# PumpMinder_v2_1.net
KiCad netlist of a schematic drawn in Altium Designer
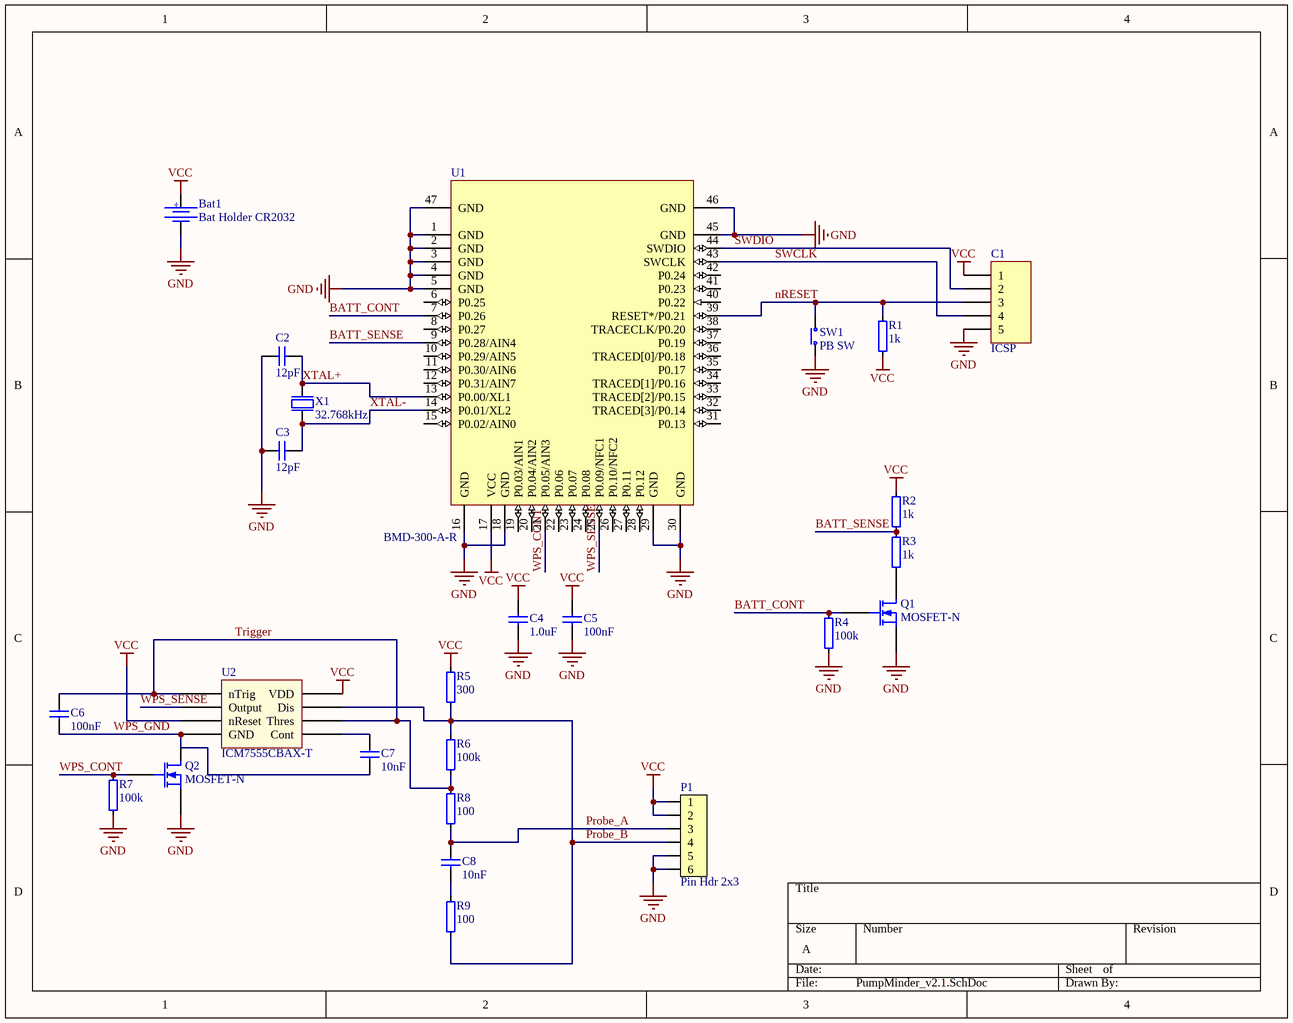
[diagram p0: PumpMinder_v2.1.SchDoc]

(export (version "E")
  (design (tool "Eeschema 10.0.6"))
  (components
    (comp (ref "Bat1")
      (value "Bat Holder CR2032")
      (footprint "CR2032_HOLDER_SMD")
      (description "Bat Holder CR2032 SMD")
      (fields
        (field (name "MANUFACTURER") "Keystone")
        (field (name "MANUFACTURER PART NUMBER") "3002")
        (field (name "PUBLISHER") "Nordic Semiconductor")
      )
      (libsource (lib "pca10040") (part "Battery"))
    )
    (comp (ref "C1") (value "ICSP") (footprint "TC2030-MCP") (libsource (lib "TC2030") (part "ICSP")))
    (comp (ref "C2")
      (value "12pF")
      (footprint "CAPC1005X04L")
      (description "Capacitor, NP0, ±0.1pF")
      (fields (field (name "PART NUMBER") "C0402-1.2p") (field (name "PUBLISHER") "Nordic Semiconductor"))
      (libsource (lib "pca10040") (part "CAP_0402"))
    )
    (comp (ref "C3")
      (value "12pF")
      (footprint "CAPC1005X04L")
      (description "Capacitor, NP0, ±0.1pF")
      (fields (field (name "PART NUMBER") "C0402-1.2p") (field (name "PUBLISHER") "Nordic Semiconductor"))
      (libsource (lib "pca10040") (part "CAP_0402"))
    )
    (comp (ref "C4")
      (value "1.0uF")
      (footprint "CAPC1608X06L")
      (description "Capacitor, X5R, ±10%")
      (fields (field (name "PART NUMBER") "C0603-4µ7") (field (name "PUBLISHER") "Nordic Semiconductor"))
      (libsource (lib "pca10040") (part "CAP_0603"))
    )
    (comp (ref "C5")
      (value "100nF")
      (footprint "CAPC1005X04L")
      (description "Capacitor, NP0, ±0.1pF")
      (fields (field (name "PART NUMBER") "C0402-1.2p") (field (name "PUBLISHER") "Nordic Semiconductor"))
      (libsource (lib "pca10040") (part "CAP_0402"))
    )
    (comp (ref "C6")
      (value "100nF")
      (footprint "CAPC1005X04L")
      (description "Capacitor, NP0, ±0.1pF")
      (fields (field (name "PART NUMBER") "C0402-1.2p") (field (name "PUBLISHER") "Nordic Semiconductor"))
      (libsource (lib "pca10040") (part "CAP_0402"))
    )
    (comp (ref "C7")
      (value "10nF")
      (footprint "CAPC1005X04L")
      (description "Capacitor, NP0, ±0.1pF")
      (fields (field (name "PART NUMBER") "C0402-1.2p") (field (name "PUBLISHER") "Nordic Semiconductor"))
      (libsource (lib "pca10040") (part "CAP_0402"))
    )
    (comp (ref "C8")
      (value "10nF")
      (footprint "CAPC1005X04L")
      (description "Capacitor, NP0, ±0.1pF")
      (fields (field (name "PART NUMBER") "C0402-1.2p") (field (name "PUBLISHER") "Nordic Semiconductor"))
      (libsource (lib "pca10040") (part "CAP_0402"))
    )
    (comp (ref "P1")
      (value "Pin Hdr 2x3")
      (footprint "Molex 15-91-2060")
      (description "Pin Header 2x3, 2.54mm (100mil) SMD")
      (fields
        (field (name "PART NUMBER") "Pin Header 2x3 SMD")
        (field (name "MANUFACTURER") "Molex")
        (field (name "PUBLISHER") "Nordic Semiconductor")
      )
      (libsource (lib "pca10040") (part "Pin Header 2x3 SMD"))
    )
    (comp (ref "Q1")
      (value "MOSFET-N")
      (footprint "SOT-23_L")
      (description "N-Channel MOSFET")
      (fields (field (name "PUBLISHER") "Altium Limited"))
      (libsource (lib "Custom_Library") (part "MOSFET-N"))
    )
    (comp (ref "Q2")
      (value "MOSFET-N")
      (footprint "SOT-23_L")
      (description "N-Channel MOSFET")
      (fields (field (name "PUBLISHER") "Altium Limited"))
      (libsource (lib "Custom_Library") (part "MOSFET-N"))
    )
    (comp (ref "R1")
      (value "1k")
      (footprint "RESC1005X04L")
      (description "Not mounted")
      (fields (field (name "PART NUMBER") "R0402-N.C.") (field (name "PUBLISHER") "Nordic Semiconductor"))
      (libsource (lib "pca10040") (part "RES_0402"))
    )
    (comp (ref "R2")
      (value "1k")
      (footprint "RESC1005X04L")
      (description "Not mounted")
      (fields (field (name "PART NUMBER") "R0402-N.C.") (field (name "PUBLISHER") "Nordic Semiconductor"))
      (libsource (lib "pca10040") (part "RES_0402"))
    )
    (comp (ref "R3")
      (value "1k")
      (footprint "RESC1005X04L")
      (description "Not mounted")
      (fields (field (name "PART NUMBER") "R0402-N.C.") (field (name "PUBLISHER") "Nordic Semiconductor"))
      (libsource (lib "pca10040") (part "RES_0402"))
    )
    (comp (ref "R4")
      (value "100k")
      (footprint "RESC1005X04L")
      (description "Not mounted")
      (fields (field (name "PART NUMBER") "R0402-N.C.") (field (name "PUBLISHER") "Nordic Semiconductor"))
      (libsource (lib "pca10040") (part "RES_0402"))
    )
    (comp (ref "R5")
      (value "300")
      (footprint "RESC1005X04L")
      (description "Not mounted")
      (fields (field (name "PART NUMBER") "R0402-N.C.") (field (name "PUBLISHER") "Nordic Semiconductor"))
      (libsource (lib "pca10040") (part "RES_0402"))
    )
    (comp (ref "R6")
      (value "100k")
      (footprint "RESC1005X04L")
      (description "Not mounted")
      (fields (field (name "PART NUMBER") "R0402-N.C.") (field (name "PUBLISHER") "Nordic Semiconductor"))
      (libsource (lib "pca10040") (part "RES_0402"))
    )
    (comp (ref "R7")
      (value "100k")
      (footprint "RESC1005X04L")
      (description "Not mounted")
      (fields (field (name "PART NUMBER") "R0402-N.C.") (field (name "PUBLISHER") "Nordic Semiconductor"))
      (libsource (lib "pca10040") (part "RES_0402"))
    )
    (comp (ref "R8")
      (value "100")
      (footprint "RESC1005X04L")
      (description "Not mounted")
      (fields (field (name "PART NUMBER") "R0402-N.C.") (field (name "PUBLISHER") "Nordic Semiconductor"))
      (libsource (lib "pca10040") (part "RES_0402"))
    )
    (comp (ref "R9")
      (value "100")
      (footprint "RESC1005X04L")
      (description "Not mounted")
      (fields (field (name "PART NUMBER") "R0402-N.C.") (field (name "PUBLISHER") "Nordic Semiconductor"))
      (libsource (lib "pca10040") (part "RES_0402"))
    )
    (comp (ref "SW1")
      (value "PB SW")
      (footprint "ALPS_SKHUxxx010_WO_GND")
      (description "ALPS - SKHUALE010 - Tactile Switch, SPNO, SMD, 6.5x6.2x2.5mm")
      (fields
        (field (name "PART NUMBER") "ALPS_SKHUALE010")
        (field (name "MANUFACTURER") "Alps")
        (field (name "PUBLISHER") "Nordic Semiconductor")
      )
      (libsource (lib "pca10040") (part "SW-PB"))
    )
    (comp (ref "U1")
      (value "BMD-300")
      (footprint "BMD-300")
      (description "Bluetooth 4.2 LE Module, nRF52832, 512kB Flash, 64kB RAM")
      (fields
        (field (name "PART NUMBER") "BMD-300-A")
        (field (name "MANUFACTURER") "Rigado")
        (field (name "MANUFACTURER P/N") "BMD-300-A-R")
        (field (name "ADDED BY") "Cam N")
      )
      (libsource (lib "BMD-300") (part "BMD-300-A"))
    )
    (comp (ref "U2")
      (value "ICM7555CBAX-T")
      (footprint "SOIC127P600X175-8N")
      (libsource (lib "Custom_Library") (part "555 Timer"))
    )
    (comp (ref "X1")
      (value "32.768kHz")
      (footprint "XTAL_3215")
      (description "EPSON TOYOCOM - FC-135 32.768KHZ ±20PPM,9.0PF - CRYSTAL, SM, WATCH")
      (fields
        (field (name "PART NUMBER") "XTAL_FC-135 32.768k")
        (field (name "MANUFACTURER") "Epson Toyocom")
        (field (name "PUBLISHER") "Nordic Semiconductor")
      )
      (libsource (lib "pca10040") (part "XTAL_SMD3215"))
    )
  )
  (nets
    (net (code "1") (name "/BATT_CONT") (class "Default")
      (node (ref "Q1") (pin "2") (pinfunction "G_2") (pintype "passive"))
      (node (ref "R4") (pin "1") (pinfunction "1_1") (pintype "passive"))
      (node (ref "U1") (pin "7") (pinfunction "P0.26_7") (pintype "bidirectional"))
    )
    (net (code "2") (name "/BATT_SENSE") (class "Default")
      (node (ref "R2") (pin "2") (pinfunction "2_2") (pintype "passive"))
      (node (ref "R3") (pin "1") (pinfunction "1_1") (pintype "passive"))
      (node (ref "U1") (pin "9") (pinfunction "P0.28/AIN4_9") (pintype "bidirectional"))
    )
    (net (code "3") (name "/Probe_A") (class "Default")
      (node (ref "C8") (pin "1") (pinfunction "1_1") (pintype "passive"))
      (node (ref "P1") (pin "3") (pinfunction "3_3") (pintype "power_in"))
      (node (ref "R8") (pin "1") (pinfunction "1_1") (pintype "passive"))
    )
    (net (code "4") (name "/Probe_B") (class "Default")
      (node (ref "P1") (pin "4") (pinfunction "4_4") (pintype "power_in"))
      (node (ref "R5") (pin "1") (pinfunction "1_1") (pintype "passive"))
      (node (ref "R6") (pin "2") (pinfunction "2_2") (pintype "passive"))
      (node (ref "R9") (pin "1") (pinfunction "1_1") (pintype "passive"))
      (node (ref "U2") (pin "7") (pinfunction "Dis_7") (pintype "passive"))
    )
    (net (code "5") (name "/SWCLK") (class "Default")
      (node (ref "C1") (pin "4") (pinfunction "4_4") (pintype "passive"))
      (node (ref "U1") (pin "43") (pinfunction "SWCLK_43") (pintype "bidirectional"))
    )
    (net (code "6") (name "/SWDIO") (class "Default")
      (node (ref "C1") (pin "2") (pinfunction "2_2") (pintype "passive"))
      (node (ref "U1") (pin "44") (pinfunction "SWDIO_44") (pintype "bidirectional"))
    )
    (net (code "7") (name "/Trigger") (class "Default")
      (node (ref "C6") (pin "1") (pinfunction "1_1") (pintype "passive"))
      (node (ref "R6") (pin "1") (pinfunction "1_1") (pintype "passive"))
      (node (ref "R8") (pin "2") (pinfunction "2_2") (pintype "passive"))
      (node (ref "U2") (pin "2") (pinfunction "nTrig_2") (pintype "passive"))
      (node (ref "U2") (pin "6") (pinfunction "Thres_6") (pintype "passive"))
    )
    (net (code "8") (name "/WPS_CONT") (class "Default")
      (node (ref "Q2") (pin "2") (pinfunction "G_2") (pintype "passive"))
      (node (ref "R7") (pin "1") (pinfunction "1_1") (pintype "passive"))
      (node (ref "U1") (pin "21") (pinfunction "P0.05/AIN3_21") (pintype "bidirectional"))
    )
    (net (code "9") (name "/WPS_GND") (class "Default")
      (node (ref "C6") (pin "2") (pinfunction "2_2") (pintype "passive"))
      (node (ref "C7") (pin "2") (pinfunction "2_2") (pintype "passive"))
      (node (ref "Q2") (pin "1") (pinfunction "D_1") (pintype "passive"))
      (node (ref "U2") (pin "1") (pinfunction "GND_1") (pintype "passive"))
    )
    (net (code "10") (name "/WPS_SENSE") (class "Default")
      (node (ref "U1") (pin "25") (pinfunction "P0.09/NFC1_25") (pintype "bidirectional"))
      (node (ref "U2") (pin "3") (pinfunction "Output_3") (pintype "passive"))
    )
    (net (code "11") (name "/XTAL+") (class "Default")
      (node (ref "C2") (pin "2") (pinfunction "2_2") (pintype "passive"))
      (node (ref "U1") (pin "13") (pinfunction "P0.00/XL1_13") (pintype "bidirectional"))
      (node (ref "X1") (pin "2") (pinfunction "out_2") (pintype "passive"))
    )
    (net (code "12") (name "/XTAL-") (class "Default")
      (node (ref "C3") (pin "2") (pinfunction "2_2") (pintype "passive"))
      (node (ref "U1") (pin "14") (pinfunction "P0.01/XL2_14") (pintype "bidirectional"))
      (node (ref "X1") (pin "1") (pinfunction "inp_1") (pintype "passive"))
    )
    (net (code "13") (name "/nRESET") (class "Default")
      (node (ref "C1") (pin "3") (pinfunction "3_3") (pintype "passive"))
      (node (ref "R1") (pin "1") (pinfunction "1_1") (pintype "passive"))
      (node (ref "SW1") (pin "1") (pinfunction "N.O_1") (pintype "passive"))
      (node (ref "U1") (pin "39") (pinfunction "RESET*/P0.21_39") (pintype "bidirectional"))
    )
    (net (code "14") (name "GND") (class "Default")
      (node (ref "Bat1") (pin "2") (pintype "passive"))
      (node (ref "C1") (pin "5") (pinfunction "5_5") (pintype "passive"))
      (node (ref "C2") (pin "1") (pinfunction "1_1") (pintype "passive"))
      (node (ref "C3") (pin "1") (pinfunction "1_1") (pintype "passive"))
      (node (ref "C4") (pin "1") (pinfunction "1_1") (pintype "passive"))
      (node (ref "C5") (pin "1") (pinfunction "1_1") (pintype "passive"))
      (node (ref "P1") (pin "5") (pinfunction "5_5") (pintype "power_in"))
      (node (ref "P1") (pin "6") (pinfunction "6_6") (pintype "power_in"))
      (node (ref "Q1") (pin "3") (pinfunction "S_3") (pintype "passive"))
      (node (ref "Q2") (pin "3") (pinfunction "S_3") (pintype "passive"))
      (node (ref "R4") (pin "2") (pinfunction "2_2") (pintype "passive"))
      (node (ref "R7") (pin "2") (pinfunction "2_2") (pintype "passive"))
      (node (ref "SW1") (pin "2") (pinfunction "COM_2") (pintype "passive"))
      (node (ref "U1") (pin "1") (pinfunction "GND_1") (pintype "power_in"))
      (node (ref "U1") (pin "16") (pinfunction "GND_16") (pintype "power_in"))
      (node (ref "U1") (pin "18") (pinfunction "GND_18") (pintype "power_in"))
      (node (ref "U1") (pin "2") (pinfunction "GND_2") (pintype "power_in"))
      (node (ref "U1") (pin "29") (pinfunction "GND_29") (pintype "power_in"))
      (node (ref "U1") (pin "3") (pinfunction "GND_3") (pintype "power_in"))
      (node (ref "U1") (pin "30") (pinfunction "GND_30") (pintype "power_in"))
      (node (ref "U1") (pin "4") (pinfunction "GND_4") (pintype "power_in"))
      (node (ref "U1") (pin "45") (pinfunction "GND_45") (pintype "power_in"))
      (node (ref "U1") (pin "46") (pinfunction "GND_46") (pintype "power_in"))
      (node (ref "U1") (pin "47") (pinfunction "GND_47") (pintype "power_in"))
      (node (ref "U1") (pin "5") (pinfunction "GND_5") (pintype "power_in"))
    )
    (net (code "15") (name "Net-(C8-Pad2)") (class "Default")
      (node (ref "C8") (pin "2") (pinfunction "2_2") (pintype "passive"))
      (node (ref "R9") (pin "2") (pinfunction "2_2") (pintype "passive"))
    )
    (net (code "16") (name "Net-(Q1-D)") (class "Default")
      (node (ref "Q1") (pin "1") (pinfunction "D_1") (pintype "passive"))
      (node (ref "R3") (pin "2") (pinfunction "2_2") (pintype "passive"))
    )
    (net (code "17") (name "Net-(U2-Cont)") (class "Default")
      (node (ref "C7") (pin "1") (pinfunction "1_1") (pintype "passive"))
      (node (ref "U2") (pin "5") (pinfunction "Cont_5") (pintype "passive"))
    )
    (net (code "18") (name "VCC") (class "Default")
      (node (ref "Bat1") (pin "1") (pintype "passive"))
      (node (ref "C1") (pin "1") (pinfunction "1_1") (pintype "passive"))
      (node (ref "C4") (pin "2") (pinfunction "2_2") (pintype "passive"))
      (node (ref "C5") (pin "2") (pinfunction "2_2") (pintype "passive"))
      (node (ref "P1") (pin "1") (pinfunction "1_1") (pintype "passive"))
      (node (ref "P1") (pin "2") (pinfunction "2_2") (pintype "passive"))
      (node (ref "R1") (pin "2") (pinfunction "2_2") (pintype "passive"))
      (node (ref "R2") (pin "1") (pinfunction "1_1") (pintype "passive"))
      (node (ref "R5") (pin "2") (pinfunction "2_2") (pintype "passive"))
      (node (ref "U1") (pin "17") (pinfunction "VCC_17") (pintype "power_in"))
      (node (ref "U2") (pin "4") (pinfunction "nReset_4") (pintype "passive"))
      (node (ref "U2") (pin "8") (pinfunction "VDD_8") (pintype "passive"))
    )
    (net (code "19") (name "unconnected-(U1-P0.02{slash}AIN0-Pad15)") (class "Default")
      (node (ref "U1") (pin "15") (pinfunction "P0.02/AIN0_15") (pintype "bidirectional"))
    )
    (net (code "20") (name "unconnected-(U1-P0.03{slash}AIN1-Pad19)") (class "Default")
      (node (ref "U1") (pin "19") (pinfunction "P0.03/AIN1_19") (pintype "bidirectional"))
    )
    (net (code "21") (name "unconnected-(U1-P0.04{slash}AIN2-Pad20)") (class "Default")
      (node (ref "U1") (pin "20") (pinfunction "P0.04/AIN2_20") (pintype "bidirectional"))
    )
    (net (code "22") (name "unconnected-(U1-P0.06-Pad22)") (class "Default")
      (node (ref "U1") (pin "22") (pinfunction "P0.06_22") (pintype "bidirectional"))
    )
    (net (code "23") (name "unconnected-(U1-P0.07-Pad23)") (class "Default")
      (node (ref "U1") (pin "23") (pinfunction "P0.07_23") (pintype "bidirectional"))
    )
    (net (code "24") (name "unconnected-(U1-P0.08-Pad24)") (class "Default")
      (node (ref "U1") (pin "24") (pinfunction "P0.08_24") (pintype "bidirectional"))
    )
    (net (code "25") (name "unconnected-(U1-P0.10{slash}NFC2-Pad26)") (class "Default")
      (node (ref "U1") (pin "26") (pinfunction "P0.10/NFC2_26") (pintype "bidirectional"))
    )
    (net (code "26") (name "unconnected-(U1-P0.11-Pad27)") (class "Default")
      (node (ref "U1") (pin "27") (pinfunction "P0.11_27") (pintype "bidirectional"))
    )
    (net (code "27") (name "unconnected-(U1-P0.12-Pad28)") (class "Default")
      (node (ref "U1") (pin "28") (pinfunction "P0.12_28") (pintype "bidirectional"))
    )
    (net (code "28") (name "unconnected-(U1-P0.13-Pad31)") (class "Default")
      (node (ref "U1") (pin "31") (pinfunction "P0.13_31") (pintype "bidirectional"))
    )
    (net (code "29") (name "unconnected-(U1-P0.17-Pad35)") (class "Default")
      (node (ref "U1") (pin "35") (pinfunction "P0.17_35") (pintype "bidirectional"))
    )
    (net (code "30") (name "unconnected-(U1-P0.19-Pad37)") (class "Default")
      (node (ref "U1") (pin "37") (pinfunction "P0.19_37") (pintype "bidirectional"))
    )
    (net (code "31") (name "unconnected-(U1-P0.22-Pad40)") (class "Default")
      (node (ref "U1") (pin "40") (pinfunction "P0.22_40") (pintype "input"))
    )
    (net (code "32") (name "unconnected-(U1-P0.23-Pad41)") (class "Default")
      (node (ref "U1") (pin "41") (pinfunction "P0.23_41") (pintype "bidirectional"))
    )
    (net (code "33") (name "unconnected-(U1-P0.24-Pad42)") (class "Default")
      (node (ref "U1") (pin "42") (pinfunction "P0.24_42") (pintype "bidirectional"))
    )
    (net (code "34") (name "unconnected-(U1-P0.25-Pad6)") (class "Default")
      (node (ref "U1") (pin "6") (pinfunction "P0.25_6") (pintype "bidirectional"))
    )
    (net (code "35") (name "unconnected-(U1-P0.27-Pad8)") (class "Default")
      (node (ref "U1") (pin "8") (pinfunction "P0.27_8") (pintype "bidirectional"))
    )
    (net (code "36") (name "unconnected-(U1-P0.29{slash}AIN5-Pad10)") (class "Default")
      (node (ref "U1") (pin "10") (pinfunction "P0.29/AIN5_10") (pintype "bidirectional"))
    )
    (net (code "37") (name "unconnected-(U1-P0.30{slash}AIN6-Pad11)") (class "Default")
      (node (ref "U1") (pin "11") (pinfunction "P0.30/AIN6_11") (pintype "bidirectional"))
    )
    (net (code "38") (name "unconnected-(U1-P0.31{slash}AIN7-Pad12)") (class "Default")
      (node (ref "U1") (pin "12") (pinfunction "P0.31/AIN7_12") (pintype "bidirectional"))
    )
    (net (code "39") (name "unconnected-(U1-TRACECLK{slash}P0.20-Pad38)") (class "Default")
      (node (ref "U1") (pin "38") (pinfunction "TRACECLK/P0.20_38") (pintype "bidirectional"))
    )
    (net (code "40") (name "unconnected-(U1-TRACED[0]{slash}P0.18-Pad36)") (class "Default")
      (node (ref "U1") (pin "36") (pinfunction "TRACED[0]/P0.18_36") (pintype "bidirectional"))
    )
    (net (code "41") (name "unconnected-(U1-TRACED[1]{slash}P0.16-Pad34)") (class "Default")
      (node (ref "U1") (pin "34") (pinfunction "TRACED[1]/P0.16_34") (pintype "bidirectional"))
    )
    (net (code "42") (name "unconnected-(U1-TRACED[2]{slash}P0.15-Pad33)") (class "Default")
      (node (ref "U1") (pin "33") (pinfunction "TRACED[2]/P0.15_33") (pintype "bidirectional"))
    )
    (net (code "43") (name "unconnected-(U1-TRACED[3]{slash}P0.14-Pad32)") (class "Default")
      (node (ref "U1") (pin "32") (pinfunction "TRACED[3]/P0.14_32") (pintype "bidirectional"))
    )
  )
)
